# power_supply.net
KiCad netlist of a schematic drawn in Altium Designer
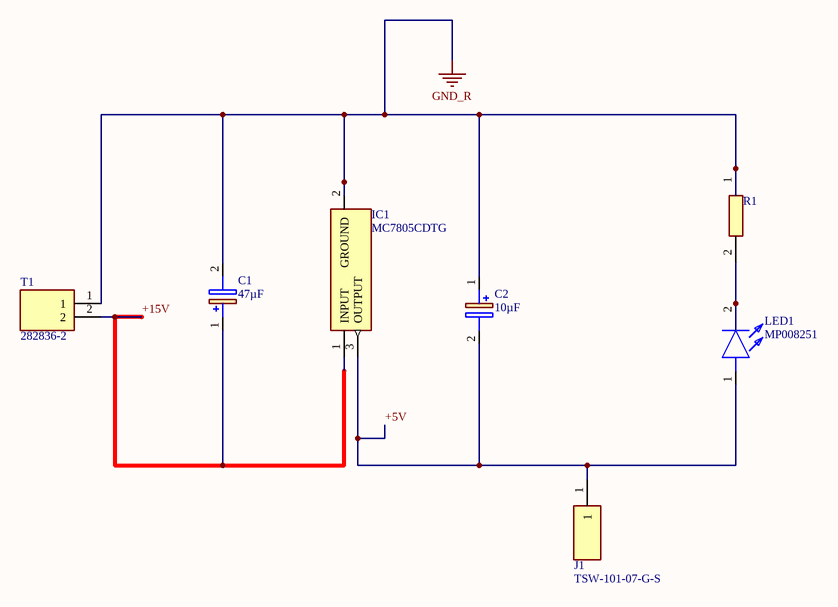
[diagram p0: power_supply.SchDoc]

(export (version "E")
  (design (tool "Eeschema 10.0.6"))
  (components
    (comp (ref "C1")
      (value "47µF")
      (footprint "CAPAE1030X1050N")
      (fields
        (field (name "MANUFACTURER_PART_NUMBER") "UUX2A470MNL1GS")
        (field (name "MOUSER PART NUMBER") "647-UUX2A470MNL1GS")
      )
      (libsource (lib "") (part "TPSC106K025R0500_1"))
    )
    (comp (ref "C2")
      (value "10µF")
      (footprint "CAPPM6032X280N")
      (description "Capacitor, 10 µF, \r\n25 V, 2312 [6032 \r\nMetric], ± 10%, 0.5 \r\nohm, C")
      (fields
        (field (name "MANUFACTURER_PART_NUMBER") "TPSC106K025R0500")
        (field (name "MOUSER PART NUMBER") "581-TPSC106K025R0500")
      )
      (libsource (lib "Jithendra Pambali") (part "TPSC106K025R0500"))
    )
    (comp (ref "IC1")
      (value "MC7805CDTG")
      (footprint "MC7915ACD2TG")
      (description "Integrated Circuit")
      (fields (field (name "MOUSER PART NUMBER") "863-MC7805CDTG") (field (name "SOURCE") "RIL_SCH.SchLib"))
      (libsource (lib "Jithendra Pambali") (part "MC7805CDTG"))
    )
    (comp (ref "J1")
      (value "TSW-101-07-G-S")
      (footprint "TSW-101-XX-YY-S")
      (description "Connector")
      (fields (field (name "MOUSER PART NUMBER") "200-TSW10107GS"))
      (libsource (lib "Jithendra Pambali") (part "TSW-101-07-G-S"))
    )
    (comp (ref "LED1")
      (value "MP008251")
      (footprint "SM0603SRC")
      (description "LED")
      (libsource (lib "Jithendra Pambali") (part "SM0603SRC"))
    )
    (comp (ref "R1")
      (value "CRCW2010100KFKEF")
      (footprint "RESC5025X71N")
      (description "Resistor")
      (fields (field (name "MOUSER PART NUMBER") "71-CRCW2010-100K-E3"))
      (libsource (lib "Jithendra Pambali") (part "CRCW2010100KFKEF"))
    )
    (comp (ref "T1")
      (value "282836-2")
      (footprint "2828362")
      (description "Connector")
      (fields (field (name "MOUSER PART NUMBER") "571-2828362"))
      (libsource (lib "Jithendra Pambali") (part "282836-2"))
    )
  )
  (nets
    (net (code "1") (name "/+5V") (class "Default")
      (node (ref "C2") (pin "2") (pinfunction "-_2") (pintype "passive"))
      (node (ref "IC1") (pin "3") (pinfunction "OUTPUT_3") (pintype "output"))
      (node (ref "J1") (pin "1") (pinfunction "1_1") (pintype "passive"))
      (node (ref "LED1") (pin "1") (pinfunction "A_1") (pintype "passive"))
    )
    (net (code "2") (name "/+15V") (class "Default")
      (node (ref "C1") (pin "1") (pinfunction "+_1") (pintype "passive"))
      (node (ref "IC1") (pin "1") (pinfunction "INPUT_1") (pintype "passive"))
      (node (ref "T1") (pin "2") (pinfunction "2_2") (pintype "passive"))
    )
    (net (code "3") (name "GND_R") (class "Default")
      (node (ref "C1") (pin "2") (pinfunction "-_2") (pintype "passive"))
      (node (ref "C2") (pin "1") (pinfunction "+_1") (pintype "passive"))
      (node (ref "IC1") (pin "2") (pinfunction "GROUND_2") (pintype "passive"))
      (node (ref "R1") (pin "1") (pinfunction "1_1") (pintype "passive"))
      (node (ref "T1") (pin "1") (pinfunction "1_1") (pintype "passive"))
    )
    (net (code "4") (name "Net-(LED1-K)") (class "Default")
      (node (ref "LED1") (pin "2") (pinfunction "K_2") (pintype "passive"))
      (node (ref "R1") (pin "2") (pinfunction "2_2") (pintype "passive"))
    )
  )
)
